# RawWaves_v1-1.net
KiCad netlist of a schematic drawn in EAGLE
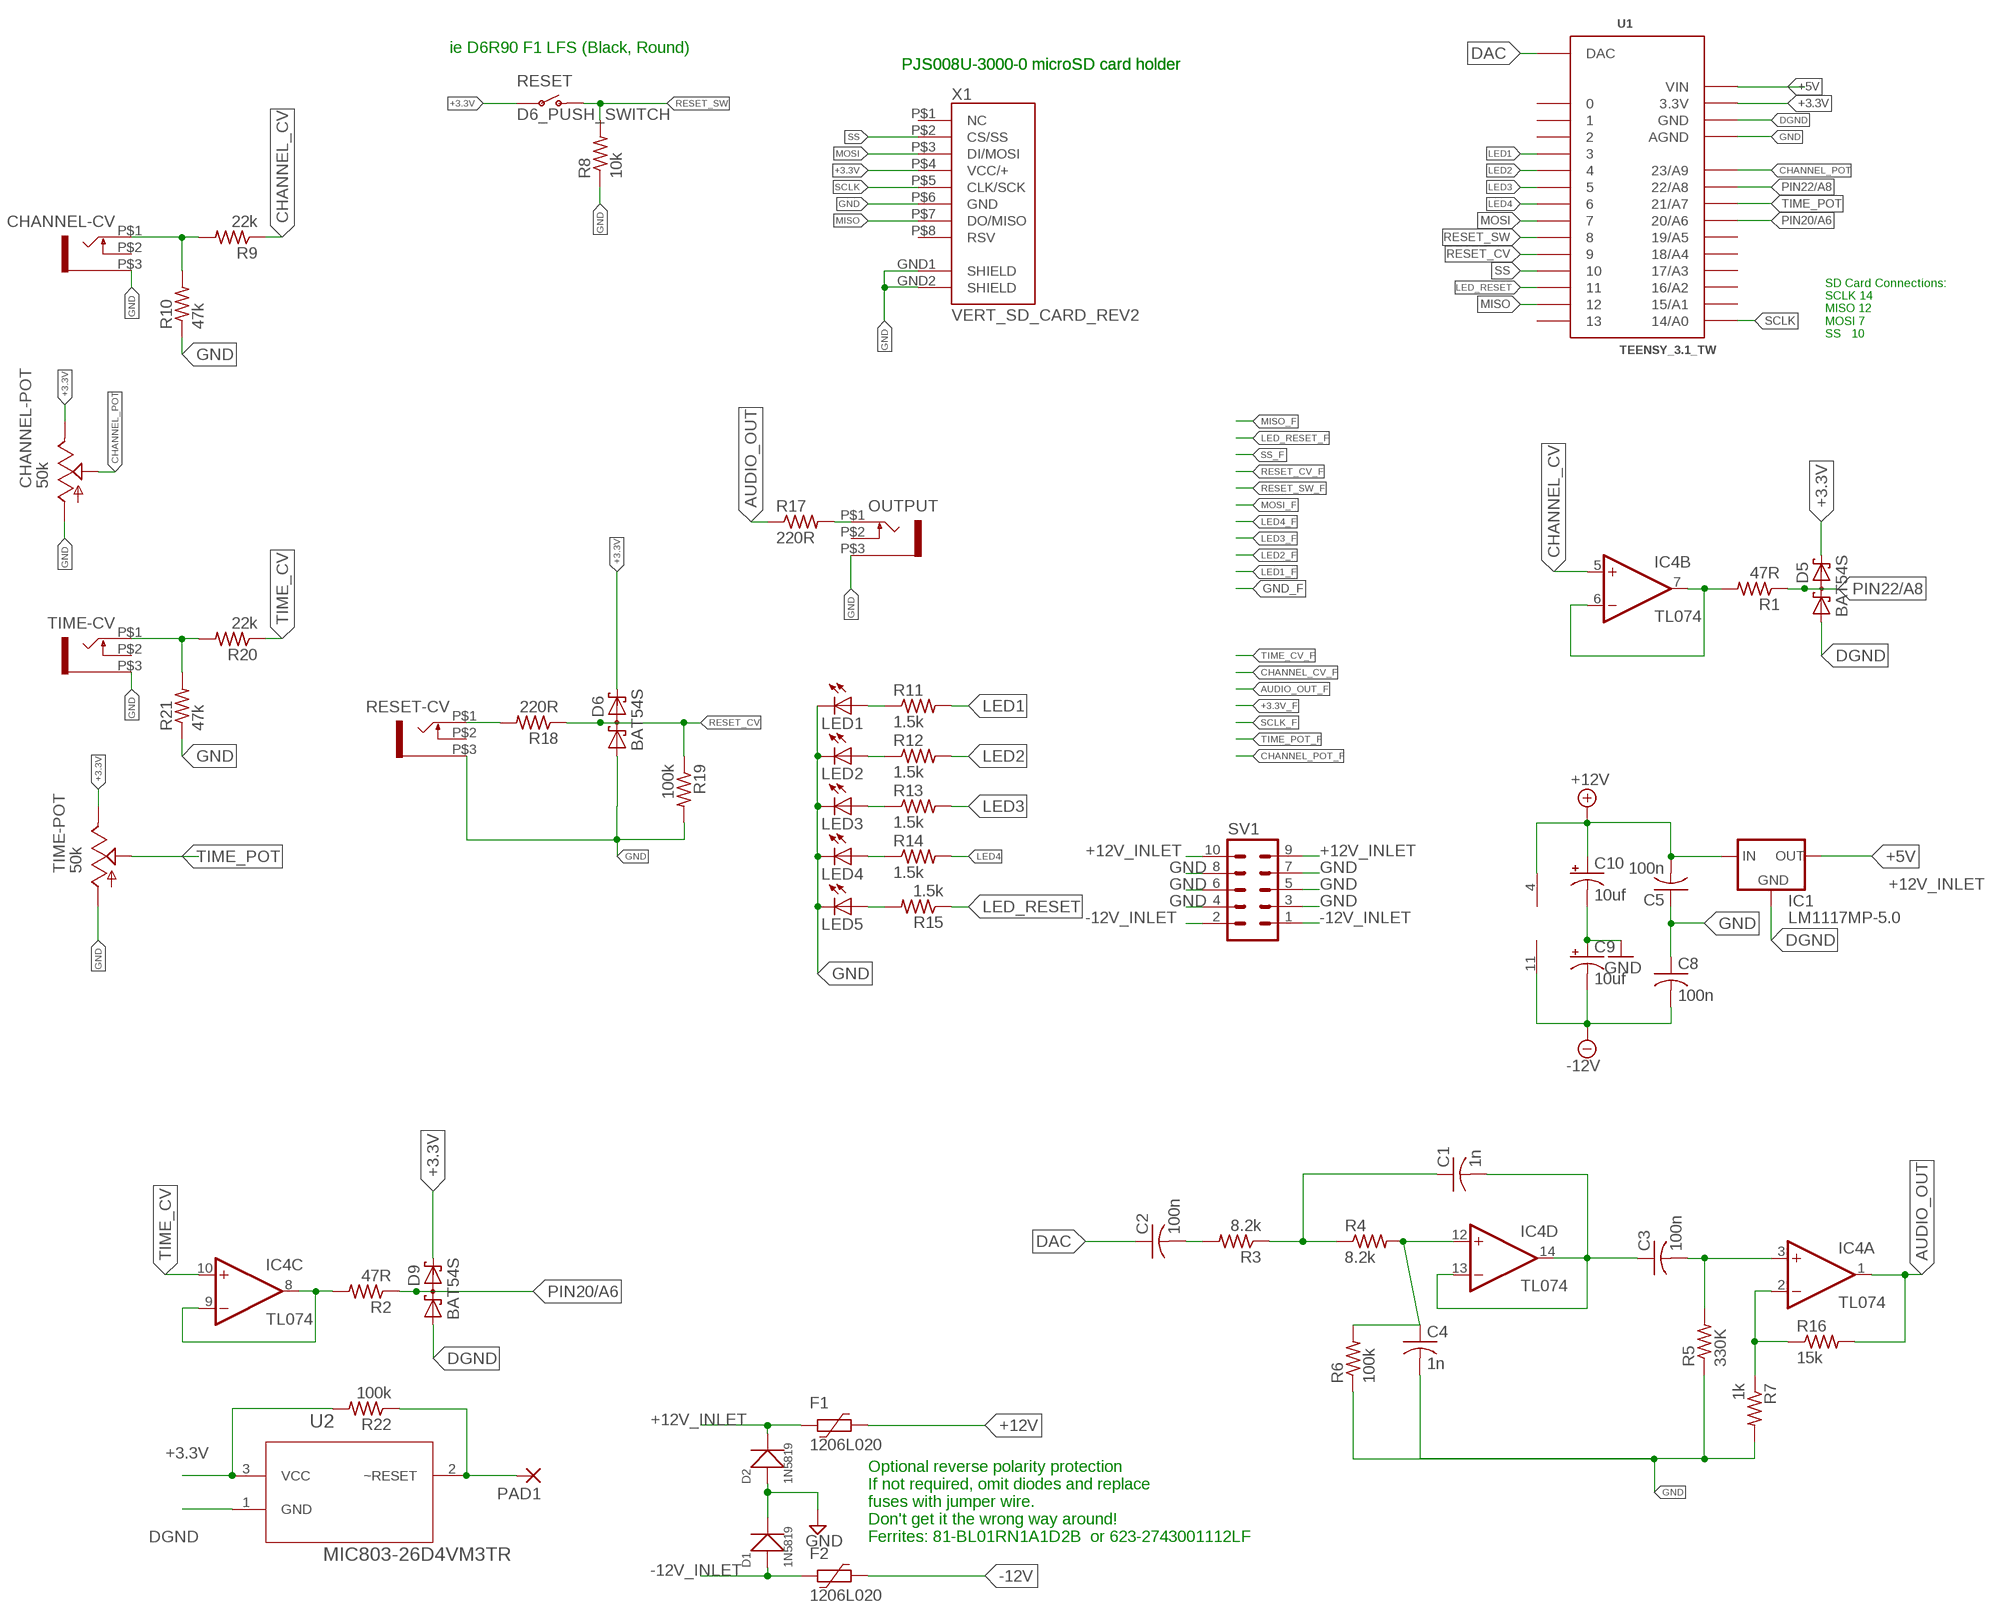
[diagram p0: schematic, sheet 1]

(export (version "E")
  (design (tool "Eeschema 10.0.6"))
  (components
    (comp (ref "C1")
      (value "1n")
      (footprint "eagle-import:C0805")
      (libsource (lib "eagle-import") (part "C-USC0805"))
    )
    (comp (ref "C2")
      (value "100n")
      (footprint "eagle-import:C0805")
      (libsource (lib "eagle-import") (part "C-USC0805"))
    )
    (comp (ref "C3")
      (value "100n")
      (footprint "eagle-import:C0805")
      (libsource (lib "eagle-import") (part "C-USC0805"))
    )
    (comp (ref "C4")
      (value "1n")
      (footprint "eagle-import:C0805")
      (libsource (lib "eagle-import") (part "C-USC0805"))
    )
    (comp (ref "C5")
      (value "100n")
      (footprint "eagle-import:C0805")
      (libsource (lib "eagle-import") (part "C-USC0805"))
    )
    (comp (ref "C8")
      (value "100n")
      (footprint "eagle-import:C0805")
      (libsource (lib "eagle-import") (part "C-USC0805"))
    )
    (comp (ref "C9")
      (value "10uf")
      (footprint "eagle-import:PANASONIC_B")
      (libsource (lib "eagle-import") (part "CPOL-USB"))
    )
    (comp (ref "C10")
      (value "10uf")
      (footprint "eagle-import:PANASONIC_B")
      (libsource (lib "eagle-import") (part "CPOL-USB"))
    )
    (comp (ref "CHANNEL-CV")
      (value "WQP-PJ301M-12_JACK")
      (footprint "eagle-import:WQP-PJ301M-12_JACK")
      (libsource (lib "eagle-import") (part "WQP-PJ301M-12_JACK"))
    )
    (comp (ref "CHANNEL-POT")
      (value "50k")
      (footprint "eagle-import:EVUF")
      (libsource (lib "eagle-import") (part "ALPHA-9MMAF2"))
    )
    (comp (ref "D1")
      (value "1N5819")
      (footprint "eagle-import:SOD-123")
      (fields (field (name "MPN") "B0540W"))
      (libsource (lib "eagle-import") (part "SMD-DIODE-SCHOTTKY-40V-500MA(SOD-123)"))
    )
    (comp (ref "D2")
      (value "1N5819")
      (footprint "eagle-import:SOD-123")
      (fields (field (name "MPN") "B0540W"))
      (libsource (lib "eagle-import") (part "SMD-DIODE-SCHOTTKY-40V-500MA(SOD-123)"))
    )
    (comp (ref "D5")
      (value "BAT54S")
      (footprint "eagle-import:SOT23")
      (libsource (lib "eagle-import") (part "BAT54S"))
    )
    (comp (ref "D6")
      (value "BAT54S")
      (footprint "eagle-import:SOT23")
      (libsource (lib "eagle-import") (part "BAT54S"))
    )
    (comp (ref "D9")
      (value "BAT54S")
      (footprint "eagle-import:SOT23")
      (libsource (lib "eagle-import") (part "BAT54S"))
    )
    (comp (ref "F1")
      (value "1206L020")
      (footprint "eagle-import:1206L")
      (fields (field (name "MF") "Littelfuse"))
      (libsource (lib "eagle-import") (part "?1206L020"))
    )
    (comp (ref "F2")
      (value "1206L020")
      (footprint "eagle-import:1206L")
      (fields (field (name "MF") "Littelfuse"))
      (libsource (lib "eagle-import") (part "?1206L020"))
    )
    (comp (ref "IC1")
      (value "LM1117MP-5.0")
      (footprint "eagle-import:SOT223")
      (fields (field (name "MF") "Texas Instruments"))
      (libsource (lib "eagle-import") (part "LM1117?-MP5.0"))
    )
    (comp (ref "IC4")
      (value "TL074")
      (footprint "eagle-import:SO14")
      (libsource (lib "eagle-import") (part "TL074D"))
    )
    (comp (ref "LED1")
      (value "LED3MM")
      (footprint "eagle-import:LED3MM")
      (libsource (lib "eagle-import") (part "LED3MM"))
    )
    (comp (ref "LED2")
      (value "LED3MM")
      (footprint "eagle-import:LED3MM")
      (libsource (lib "eagle-import") (part "LED3MM"))
    )
    (comp (ref "LED3")
      (value "LED3MM")
      (footprint "eagle-import:LED3MM")
      (libsource (lib "eagle-import") (part "LED3MM"))
    )
    (comp (ref "LED4")
      (value "LED3MM")
      (footprint "eagle-import:LED3MM")
      (libsource (lib "eagle-import") (part "LED3MM"))
    )
    (comp (ref "LED5")
      (value "LED3MM")
      (footprint "eagle-import:LED3MM")
      (libsource (lib "eagle-import") (part "LED3MM"))
    )
    (comp (ref "OUTPUT")
      (value "WQP-PJ301M-12_JACK")
      (footprint "eagle-import:WQP-PJ301M-12_JACK")
      (libsource (lib "eagle-import") (part "WQP-PJ301M-12_JACK"))
    )
    (comp (ref "PAD1")
      (value "1,6/0,9")
      (footprint "eagle-import:1,6_0,9")
      (libsource (lib "eagle-import") (part "1,6/0,9"))
    )
    (comp (ref "R1")
      (value "47R")
      (footprint "eagle-import:R0805")
      (libsource (lib "eagle-import") (part "R-US_R0805"))
    )
    (comp (ref "R2")
      (value "47R")
      (footprint "eagle-import:R0805")
      (libsource (lib "eagle-import") (part "R-US_R0805"))
    )
    (comp (ref "R3")
      (value "8.2k")
      (footprint "eagle-import:R0805")
      (libsource (lib "eagle-import") (part "R-US_R0805"))
    )
    (comp (ref "R4")
      (value "8.2k")
      (footprint "eagle-import:R0805")
      (libsource (lib "eagle-import") (part "R-US_R0805"))
    )
    (comp (ref "R5")
      (value "330K")
      (footprint "eagle-import:R0805")
      (libsource (lib "eagle-import") (part "R-US_R0805"))
    )
    (comp (ref "R6")
      (value "100k")
      (footprint "eagle-import:R0805")
      (libsource (lib "eagle-import") (part "R-US_R0805"))
    )
    (comp (ref "R7")
      (value "1k")
      (footprint "eagle-import:R0805")
      (libsource (lib "eagle-import") (part "R-US_R0805"))
    )
    (comp (ref "R8")
      (value "10k")
      (footprint "eagle-import:R0805")
      (libsource (lib "eagle-import") (part "R-US_R0805"))
    )
    (comp (ref "R9")
      (value "22k")
      (footprint "eagle-import:R0805")
      (libsource (lib "eagle-import") (part "R-US_R0805"))
    )
    (comp (ref "R10")
      (value "47k")
      (footprint "eagle-import:R0805")
      (libsource (lib "eagle-import") (part "R-US_R0805"))
    )
    (comp (ref "R11")
      (value "1.5k")
      (footprint "eagle-import:R0805")
      (libsource (lib "eagle-import") (part "R-US_R0805"))
    )
    (comp (ref "R12")
      (value "1.5k")
      (footprint "eagle-import:R0805")
      (libsource (lib "eagle-import") (part "R-US_R0805"))
    )
    (comp (ref "R13")
      (value "1.5k")
      (footprint "eagle-import:R0805")
      (libsource (lib "eagle-import") (part "R-US_R0805"))
    )
    (comp (ref "R14")
      (value "1.5k")
      (footprint "eagle-import:R0805")
      (libsource (lib "eagle-import") (part "R-US_R0805"))
    )
    (comp (ref "R15")
      (value "1.5k")
      (footprint "eagle-import:R0805")
      (libsource (lib "eagle-import") (part "R-US_R0805"))
    )
    (comp (ref "R16")
      (value "15k")
      (footprint "eagle-import:R0805")
      (libsource (lib "eagle-import") (part "R-US_R0805"))
    )
    (comp (ref "R17")
      (value "220R")
      (footprint "eagle-import:R0805")
      (libsource (lib "eagle-import") (part "R-US_R0805"))
    )
    (comp (ref "R18")
      (value "220R")
      (footprint "eagle-import:R0805")
      (libsource (lib "eagle-import") (part "R-US_R0805"))
    )
    (comp (ref "R19")
      (value "100k")
      (footprint "eagle-import:R0805")
      (libsource (lib "eagle-import") (part "R-US_R0805"))
    )
    (comp (ref "R20")
      (value "22k")
      (footprint "eagle-import:R0805")
      (libsource (lib "eagle-import") (part "R-US_R0805"))
    )
    (comp (ref "R21")
      (value "47k")
      (footprint "eagle-import:R0805")
      (libsource (lib "eagle-import") (part "R-US_R0805"))
    )
    (comp (ref "R22")
      (value "100k")
      (footprint "eagle-import:R0805")
      (libsource (lib "eagle-import") (part "R-US_R0805"))
    )
    (comp (ref "RESET")
      (value "D6_PUSH_SWITCH")
      (footprint "eagle-import:D6_BUTTON_RND")
      (libsource (lib "eagle-import") (part "D6_PUSH_SWITCH"))
    )
    (comp (ref "RESET-CV")
      (value "WQP-PJ301M-12_JACK")
      (footprint "eagle-import:WQP-PJ301M-12_JACK")
      (libsource (lib "eagle-import") (part "WQP-PJ301M-12_JACK"))
    )
    (comp (ref "SV1")
      (value "10_PIN_HEADER")
      (footprint "eagle-import:MA05-2")
      (libsource (lib "eagle-import") (part "10_PIN_HEADER"))
    )
    (comp (ref "TIME-CV")
      (value "WQP-PJ301M-12_JACK")
      (footprint "eagle-import:WQP-PJ301M-12_JACK")
      (libsource (lib "eagle-import") (part "WQP-PJ301M-12_JACK"))
    )
    (comp (ref "TIME-POT")
      (value "50k")
      (footprint "eagle-import:EVUF")
      (libsource (lib "eagle-import") (part "ALPHA-9MMAF2"))
    )
    (comp (ref "U1")
      (value "TEENSY_3.1_TW")
      (footprint "eagle-import:TEENSY_3.1_TW")
      (libsource (lib "eagle-import") (part "TEENSY_3.1_TW"))
    )
    (comp (ref "U2")
      (value "MIC803-26D4VM3TR")
      (footprint "eagle-import:SOT95P232X110-3N")
      (libsource (lib "eagle-import") (part "MIC803-26D4VM3TR"))
    )
    (comp (ref "X1")
      (value "VERT_SD_CARD_REV2")
      (footprint "eagle-import:VERT_MICROSD_REV2")
      (libsource (lib "eagle-import") (part "VERT_SD_CARD_REV2"))
    )
  )
  (nets
    (net (code "1") (name "+3.3V") (class "Default")
      (node (ref "CHANNEL-POT") (pin "3") (pinfunction "E_3") (pintype "passive"))
      (node (ref "D5") (pin "2") (pinfunction "C2_2") (pintype "passive"))
      (node (ref "D6") (pin "2") (pinfunction "C2_2") (pintype "passive"))
      (node (ref "D9") (pin "2") (pinfunction "C2_2") (pintype "passive"))
      (node (ref "R22") (pin "2") (pinfunction "2_2") (pintype "passive"))
      (node (ref "RESET") (pin "P$3") (pinfunction "P_P$3") (pintype "passive"))
      (node (ref "RESET") (pin "P$4") (pinfunction "P_P$4") (pintype "passive"))
      (node (ref "TIME-POT") (pin "3") (pinfunction "E_3") (pintype "passive"))
      (node (ref "U1") (pin "3.3V") (pinfunction "3.3V_3.3V") (pintype "power_in"))
      (node (ref "U2") (pin "3") (pinfunction "VCC_3") (pintype "power_in"))
      (node (ref "X1") (pin "P$4") (pinfunction "VCC/+_P$4") (pintype "bidirectional"))
    )
    (net (code "3") (name "+5V") (class "Default")
      (node (ref "IC1") (pin "2") (pinfunction "OUT_2") (pintype "passive"))
      (node (ref "IC1") (pin "4") (pinfunction "OUT_4") (pintype "passive"))
      (node (ref "U1") (pin "VIN") (pinfunction "VIN_VIN") (pintype "power_in"))
    )
    (net (code "4") (name "+12V") (class "Default")
      (node (ref "C10") (pin "+") (pinfunction "+_+") (pintype "passive"))
      (node (ref "C5") (pin "2") (pinfunction "2_2") (pintype "passive"))
      (node (ref "F1") (pin "1") (pinfunction "1_1") (pintype "passive"))
      (node (ref "IC1") (pin "3") (pinfunction "IN_3") (pintype "input"))
      (node (ref "IC4") (pin "4") (pinfunction "V+_4") (pintype "power_in"))
    )
    (net (code "5") (name "-12V") (class "Default")
      (node (ref "C8") (pin "2") (pinfunction "2_2") (pintype "passive"))
      (node (ref "C9") (pin "-") (pinfunction "-_-") (pintype "passive"))
      (node (ref "F2") (pin "1") (pinfunction "1_1") (pintype "passive"))
      (node (ref "IC4") (pin "11") (pinfunction "V-_11") (pintype "power_in"))
    )
    (net (code "6") (name "/+12V_INLET") (class "Default")
      (node (ref "D2") (pin "-") (pinfunction "-_-") (pintype "passive"))
      (node (ref "F1") (pin "2") (pinfunction "2_2") (pintype "passive"))
      (node (ref "SV1") (pin "10") (pinfunction "10_10") (pintype "passive"))
      (node (ref "SV1") (pin "9") (pinfunction "9_9") (pintype "passive"))
    )
    (net (code "7") (name "/-12V_INLET") (class "Default")
      (node (ref "D1") (pin "+") (pinfunction "+_+") (pintype "passive"))
      (node (ref "F2") (pin "2") (pinfunction "2_2") (pintype "passive"))
      (node (ref "SV1") (pin "1") (pinfunction "1_1") (pintype "passive"))
      (node (ref "SV1") (pin "2") (pinfunction "2_2") (pintype "passive"))
    )
    (net (code "8") (name "AUDIO_OUT") (class "Default")
      (node (ref "IC4") (pin "1") (pinfunction "OUT_1") (pintype "output"))
      (node (ref "R16") (pin "2") (pinfunction "2_2") (pintype "passive"))
      (node (ref "R17") (pin "1") (pinfunction "1_1") (pintype "passive"))
    )
    (net (code "10") (name "CHANNEL_CV") (class "Default")
      (node (ref "IC4") (pin "5") (pinfunction "+IN_5") (pintype "input"))
      (node (ref "R9") (pin "1") (pinfunction "1_1") (pintype "passive"))
    )
    (net (code "12") (name "CHANNEL_POT") (class "Default")
      (node (ref "CHANNEL-POT") (pin "2") (pinfunction "S_2") (pintype "passive"))
      (node (ref "U1") (pin "23/A9") (pinfunction "23/A9_23/A9") (pintype "bidirectional"))
    )
    (net (code "14") (name "DAC") (class "Default")
      (node (ref "C2") (pin "1") (pinfunction "1_1") (pintype "passive"))
      (node (ref "U1") (pin "DAC") (pinfunction "DAC_DAC") (pintype "bidirectional"))
    )
    (net (code "15") (name "DGND") (class "Default")
      (node (ref "D5") (pin "1") (pinfunction "A1_1") (pintype "passive"))
      (node (ref "D9") (pin "1") (pinfunction "A1_1") (pintype "passive"))
      (node (ref "IC1") (pin "1") (pinfunction "GND_1") (pintype "input"))
      (node (ref "U1") (pin "GND") (pinfunction "GND_GND") (pintype "power_in"))
      (node (ref "U2") (pin "1") (pinfunction "GND_1") (pintype "passive"))
    )
    (net (code "16") (name "GND") (class "Default")
      (node (ref "C10") (pin "-") (pinfunction "-_-") (pintype "passive"))
      (node (ref "C4") (pin "2") (pinfunction "2_2") (pintype "passive"))
      (node (ref "C5") (pin "1") (pinfunction "1_1") (pintype "passive"))
      (node (ref "C8") (pin "1") (pinfunction "1_1") (pintype "passive"))
      (node (ref "C9") (pin "+") (pinfunction "+_+") (pintype "passive"))
      (node (ref "CHANNEL-CV") (pin "P$3") (pinfunction "1_P$3") (pintype "passive"))
      (node (ref "CHANNEL-POT") (pin "1") (pinfunction "A_1") (pintype "passive"))
      (node (ref "D1") (pin "-") (pinfunction "-_-") (pintype "passive"))
      (node (ref "D2") (pin "+") (pinfunction "+_+") (pintype "passive"))
      (node (ref "D6") (pin "1") (pinfunction "A1_1") (pintype "passive"))
      (node (ref "LED1") (pin "K") (pinfunction "C_K") (pintype "passive"))
      (node (ref "LED2") (pin "K") (pinfunction "C_K") (pintype "passive"))
      (node (ref "LED3") (pin "K") (pinfunction "C_K") (pintype "passive"))
      (node (ref "LED4") (pin "K") (pinfunction "C_K") (pintype "passive"))
      (node (ref "LED5") (pin "K") (pinfunction "C_K") (pintype "passive"))
      (node (ref "OUTPUT") (pin "P$3") (pinfunction "1_P$3") (pintype "passive"))
      (node (ref "R10") (pin "1") (pinfunction "1_1") (pintype "passive"))
      (node (ref "R19") (pin "2") (pinfunction "2_2") (pintype "passive"))
      (node (ref "R21") (pin "1") (pinfunction "1_1") (pintype "passive"))
      (node (ref "R5") (pin "1") (pinfunction "1_1") (pintype "passive"))
      (node (ref "R6") (pin "1") (pinfunction "1_1") (pintype "passive"))
      (node (ref "R7") (pin "2") (pinfunction "2_2") (pintype "passive"))
      (node (ref "R8") (pin "1") (pinfunction "1_1") (pintype "passive"))
      (node (ref "RESET-CV") (pin "P$3") (pinfunction "1_P$3") (pintype "passive"))
      (node (ref "SV1") (pin "3") (pinfunction "3_3") (pintype "passive"))
      (node (ref "SV1") (pin "4") (pinfunction "4_4") (pintype "passive"))
      (node (ref "SV1") (pin "5") (pinfunction "5_5") (pintype "passive"))
      (node (ref "SV1") (pin "6") (pinfunction "6_6") (pintype "passive"))
      (node (ref "SV1") (pin "7") (pinfunction "7_7") (pintype "passive"))
      (node (ref "SV1") (pin "8") (pinfunction "8_8") (pintype "passive"))
      (node (ref "TIME-CV") (pin "P$3") (pinfunction "1_P$3") (pintype "passive"))
      (node (ref "TIME-POT") (pin "1") (pinfunction "A_1") (pintype "passive"))
      (node (ref "U1") (pin "AGND") (pinfunction "AGND_AGND") (pintype "power_in"))
      (node (ref "X1") (pin "GND1") (pinfunction "SHIELD_GND1") (pintype "bidirectional"))
      (node (ref "X1") (pin "GND2") (pinfunction "SHIELD_GND2") (pintype "bidirectional"))
      (node (ref "X1") (pin "P$6") (pinfunction "GND_P$6") (pintype "bidirectional"))
    )
    (net (code "18") (name "LED1") (class "Default")
      (node (ref "R11") (pin "2") (pinfunction "2_2") (pintype "passive"))
      (node (ref "U1") (pin "3") (pinfunction "3_3") (pintype "bidirectional"))
    )
    (net (code "20") (name "LED2") (class "Default")
      (node (ref "R12") (pin "2") (pinfunction "2_2") (pintype "passive"))
      (node (ref "U1") (pin "4") (pinfunction "4_4") (pintype "bidirectional"))
    )
    (net (code "22") (name "LED3") (class "Default")
      (node (ref "R13") (pin "2") (pinfunction "2_2") (pintype "passive"))
      (node (ref "U1") (pin "5") (pinfunction "5_5") (pintype "bidirectional"))
    )
    (net (code "24") (name "LED4") (class "Default")
      (node (ref "R14") (pin "2") (pinfunction "2_2") (pintype "passive"))
      (node (ref "U1") (pin "6") (pinfunction "6_6") (pintype "bidirectional"))
    )
    (net (code "26") (name "LED_RESET") (class "Default")
      (node (ref "R15") (pin "1") (pinfunction "1_1") (pintype "passive"))
      (node (ref "U1") (pin "11") (pinfunction "11_11") (pintype "bidirectional"))
    )
    (net (code "28") (name "MISO") (class "Default")
      (node (ref "U1") (pin "12") (pinfunction "12_12") (pintype "bidirectional"))
      (node (ref "X1") (pin "P$7") (pinfunction "DO/MISO_P$7") (pintype "bidirectional"))
    )
    (net (code "30") (name "MOSI") (class "Default")
      (node (ref "U1") (pin "7") (pinfunction "7_7") (pintype "bidirectional"))
      (node (ref "X1") (pin "P$3") (pinfunction "DI/MOSI_P$3") (pintype "bidirectional"))
    )
    (net (code "32") (name "Net-(C1-Pad1)") (class "Default")
      (node (ref "C1") (pin "1") (pinfunction "1_1") (pintype "passive"))
      (node (ref "R3") (pin "1") (pinfunction "1_1") (pintype "passive"))
      (node (ref "R4") (pin "1") (pinfunction "1_1") (pintype "passive"))
    )
    (net (code "33") (name "Net-(C2-Pad2)") (class "Default")
      (node (ref "C2") (pin "2") (pinfunction "2_2") (pintype "passive"))
      (node (ref "R3") (pin "2") (pinfunction "2_2") (pintype "passive"))
    )
    (net (code "34") (name "Net-(CHANNEL-CV-2)") (class "Default")
      (node (ref "CHANNEL-CV") (pin "P$1") (pinfunction "2_P$1") (pintype "passive"))
      (node (ref "R10") (pin "2") (pinfunction "2_2") (pintype "passive"))
      (node (ref "R9") (pin "2") (pinfunction "2_2") (pintype "passive"))
    )
    (net (code "35") (name "Net-(IC4A-+IN)") (class "Default")
      (node (ref "C3") (pin "2") (pinfunction "2_2") (pintype "passive"))
      (node (ref "IC4") (pin "3") (pinfunction "+IN_3") (pintype "input"))
      (node (ref "R5") (pin "2") (pinfunction "2_2") (pintype "passive"))
    )
    (net (code "36") (name "Net-(IC4A--IN)") (class "Default")
      (node (ref "IC4") (pin "2") (pinfunction "-IN_2") (pintype "input"))
      (node (ref "R16") (pin "1") (pinfunction "1_1") (pintype "passive"))
      (node (ref "R7") (pin "1") (pinfunction "1_1") (pintype "passive"))
    )
    (net (code "37") (name "Net-(IC4B--IN)") (class "Default")
      (node (ref "IC4") (pin "6") (pinfunction "-IN_6") (pintype "input"))
      (node (ref "IC4") (pin "7") (pinfunction "OUT_7") (pintype "output"))
      (node (ref "R1") (pin "2") (pinfunction "2_2") (pintype "passive"))
    )
    (net (code "38") (name "Net-(IC4C--IN)") (class "Default")
      (node (ref "IC4") (pin "8") (pinfunction "OUT_8") (pintype "output"))
      (node (ref "IC4") (pin "9") (pinfunction "-IN_9") (pintype "input"))
      (node (ref "R2") (pin "2") (pinfunction "2_2") (pintype "passive"))
    )
    (net (code "39") (name "Net-(IC4D-+IN)") (class "Default")
      (node (ref "C4") (pin "1") (pinfunction "1_1") (pintype "passive"))
      (node (ref "IC4") (pin "12") (pinfunction "+IN_12") (pintype "input"))
      (node (ref "R4") (pin "2") (pinfunction "2_2") (pintype "passive"))
      (node (ref "R6") (pin "2") (pinfunction "2_2") (pintype "passive"))
    )
    (net (code "40") (name "Net-(IC4D--IN)") (class "Default")
      (node (ref "C1") (pin "2") (pinfunction "2_2") (pintype "passive"))
      (node (ref "C3") (pin "1") (pinfunction "1_1") (pintype "passive"))
      (node (ref "IC4") (pin "13") (pinfunction "-IN_13") (pintype "input"))
      (node (ref "IC4") (pin "14") (pinfunction "OUT_14") (pintype "output"))
    )
    (net (code "41") (name "Net-(LED1-PadA)") (class "Default")
      (node (ref "LED1") (pin "A") (pinfunction "A_A") (pintype "passive"))
      (node (ref "R11") (pin "1") (pinfunction "1_1") (pintype "passive"))
    )
    (net (code "42") (name "Net-(LED2-PadA)") (class "Default")
      (node (ref "LED2") (pin "A") (pinfunction "A_A") (pintype "passive"))
      (node (ref "R12") (pin "1") (pinfunction "1_1") (pintype "passive"))
    )
    (net (code "43") (name "Net-(LED3-PadA)") (class "Default")
      (node (ref "LED3") (pin "A") (pinfunction "A_A") (pintype "passive"))
      (node (ref "R13") (pin "1") (pinfunction "1_1") (pintype "passive"))
    )
    (net (code "44") (name "Net-(LED4-PadA)") (class "Default")
      (node (ref "LED4") (pin "A") (pinfunction "A_A") (pintype "passive"))
      (node (ref "R14") (pin "1") (pinfunction "1_1") (pintype "passive"))
    )
    (net (code "45") (name "Net-(LED5-PadA)") (class "Default")
      (node (ref "LED5") (pin "A") (pinfunction "A_A") (pintype "passive"))
      (node (ref "R15") (pin "2") (pinfunction "2_2") (pintype "passive"))
    )
    (net (code "46") (name "Net-(OUTPUT-2)") (class "Default")
      (node (ref "OUTPUT") (pin "P$1") (pinfunction "2_P$1") (pintype "passive"))
      (node (ref "R17") (pin "2") (pinfunction "2_2") (pintype "passive"))
    )
    (net (code "47") (name "Net-(PAD1-P)") (class "Default")
      (node (ref "PAD1") (pin "1") (pinfunction "P_1") (pintype "passive"))
      (node (ref "R22") (pin "1") (pinfunction "1_1") (pintype "passive"))
      (node (ref "U2") (pin "2") (pinfunction "~{RESET}_2") (pintype "passive"))
    )
    (net (code "48") (name "Net-(RESET-CV-2)") (class "Default")
      (node (ref "R18") (pin "2") (pinfunction "2_2") (pintype "passive"))
      (node (ref "RESET-CV") (pin "P$1") (pinfunction "2_P$1") (pintype "passive"))
    )
    (net (code "49") (name "Net-(TIME-CV-2)") (class "Default")
      (node (ref "R20") (pin "2") (pinfunction "2_2") (pintype "passive"))
      (node (ref "R21") (pin "2") (pinfunction "2_2") (pintype "passive"))
      (node (ref "TIME-CV") (pin "P$1") (pinfunction "2_P$1") (pintype "passive"))
    )
    (net (code "50") (name "PIN20{slash}A6") (class "Default")
      (node (ref "D9") (pin "3") (pinfunction "C1A2_3") (pintype "passive"))
      (node (ref "R2") (pin "1") (pinfunction "1_1") (pintype "passive"))
      (node (ref "U1") (pin "20/A6") (pinfunction "20/A6_20/A6") (pintype "bidirectional"))
    )
    (net (code "51") (name "PIN22{slash}A8") (class "Default")
      (node (ref "D5") (pin "3") (pinfunction "C1A2_3") (pintype "passive"))
      (node (ref "R1") (pin "1") (pinfunction "1_1") (pintype "passive"))
      (node (ref "U1") (pin "22/A8") (pinfunction "22/A8_22/A8") (pintype "bidirectional"))
    )
    (net (code "52") (name "RESET_CV") (class "Default")
      (node (ref "D6") (pin "3") (pinfunction "C1A2_3") (pintype "passive"))
      (node (ref "R18") (pin "1") (pinfunction "1_1") (pintype "passive"))
      (node (ref "R19") (pin "1") (pinfunction "1_1") (pintype "passive"))
      (node (ref "U1") (pin "9") (pinfunction "9_9") (pintype "bidirectional"))
    )
    (net (code "54") (name "RESET_SW") (class "Default")
      (node (ref "R8") (pin "2") (pinfunction "2_2") (pintype "passive"))
      (node (ref "RESET") (pin "P$1") (pinfunction "O_P$1") (pintype "passive"))
      (node (ref "RESET") (pin "P$2") (pinfunction "O_P$2") (pintype "passive"))
      (node (ref "U1") (pin "8") (pinfunction "8_8") (pintype "bidirectional"))
    )
    (net (code "56") (name "SCLK") (class "Default")
      (node (ref "U1") (pin "14/A0") (pinfunction "14/A0_14/A0") (pintype "bidirectional"))
      (node (ref "X1") (pin "P$5") (pinfunction "CLK/SCK_P$5") (pintype "bidirectional"))
    )
    (net (code "58") (name "SS") (class "Default")
      (node (ref "U1") (pin "10") (pinfunction "10_10") (pintype "bidirectional"))
      (node (ref "X1") (pin "P$2") (pinfunction "CS/SS_P$2") (pintype "bidirectional"))
    )
    (net (code "60") (name "TIME_CV") (class "Default")
      (node (ref "IC4") (pin "10") (pinfunction "+IN_10") (pintype "input"))
      (node (ref "R20") (pin "1") (pinfunction "1_1") (pintype "passive"))
    )
    (net (code "62") (name "TIME_POT") (class "Default")
      (node (ref "TIME-POT") (pin "2") (pinfunction "S_2") (pintype "passive"))
      (node (ref "U1") (pin "21/A7") (pinfunction "21/A7_21/A7") (pintype "bidirectional"))
    )
    (net (code "64") (name "unconnected-(CHANNEL-CV-3-PadP$2)") (class "Default")
      (node (ref "CHANNEL-CV") (pin "P$2") (pinfunction "3_P$2") (pintype "passive"))
    )
    (net (code "65") (name "unconnected-(OUTPUT-3-PadP$2)") (class "Default")
      (node (ref "OUTPUT") (pin "P$2") (pinfunction "3_P$2") (pintype "passive"))
    )
    (net (code "66") (name "unconnected-(RESET-CV-3-PadP$2)") (class "Default")
      (node (ref "RESET-CV") (pin "P$2") (pinfunction "3_P$2") (pintype "passive"))
    )
    (net (code "67") (name "unconnected-(TIME-CV-3-PadP$2)") (class "Default")
      (node (ref "TIME-CV") (pin "P$2") (pinfunction "3_P$2") (pintype "passive"))
    )
    (net (code "68") (name "unconnected-(U1-Pad0)") (class "Default")
      (node (ref "U1") (pin "0") (pinfunction "0_0") (pintype "bidirectional"))
    )
    (net (code "69") (name "unconnected-(U1-Pad1)") (class "Default")
      (node (ref "U1") (pin "1") (pinfunction "1_1") (pintype "bidirectional"))
    )
    (net (code "70") (name "unconnected-(U1-Pad2)") (class "Default")
      (node (ref "U1") (pin "2") (pinfunction "2_2") (pintype "bidirectional"))
    )
    (net (code "71") (name "unconnected-(U1-Pad13)") (class "Default")
      (node (ref "U1") (pin "13") (pinfunction "13_13") (pintype "bidirectional"))
    )
    (net (code "72") (name "unconnected-(U1-Pad15{slash}A1)") (class "Default")
      (node (ref "U1") (pin "15/A1") (pinfunction "15/A1_15/A1") (pintype "bidirectional"))
    )
    (net (code "73") (name "unconnected-(U1-Pad16{slash}A2)") (class "Default")
      (node (ref "U1") (pin "16/A2") (pinfunction "16/A2_16/A2") (pintype "bidirectional"))
    )
    (net (code "74") (name "unconnected-(U1-Pad17{slash}A3)") (class "Default")
      (node (ref "U1") (pin "17/A3") (pinfunction "17/A3_17/A3") (pintype "bidirectional"))
    )
    (net (code "75") (name "unconnected-(U1-Pad18{slash}A4)") (class "Default")
      (node (ref "U1") (pin "18/A4") (pinfunction "18/A4_18/A4") (pintype "bidirectional"))
    )
    (net (code "76") (name "unconnected-(U1-Pad19{slash}A5)") (class "Default")
      (node (ref "U1") (pin "19/A5") (pinfunction "19/A5_19/A5") (pintype "bidirectional"))
    )
    (net (code "77") (name "unconnected-(X1-NC-PadP$1)") (class "Default")
      (node (ref "X1") (pin "P$1") (pinfunction "NC_P$1") (pintype "bidirectional"))
    )
    (net (code "78") (name "unconnected-(X1-RSV-PadP$8)") (class "Default")
      (node (ref "X1") (pin "P$8") (pinfunction "RSV_P$8") (pintype "bidirectional"))
    )
  )
)
